# second_model.net
KiCad netlist of a schematic drawn in EAGLE
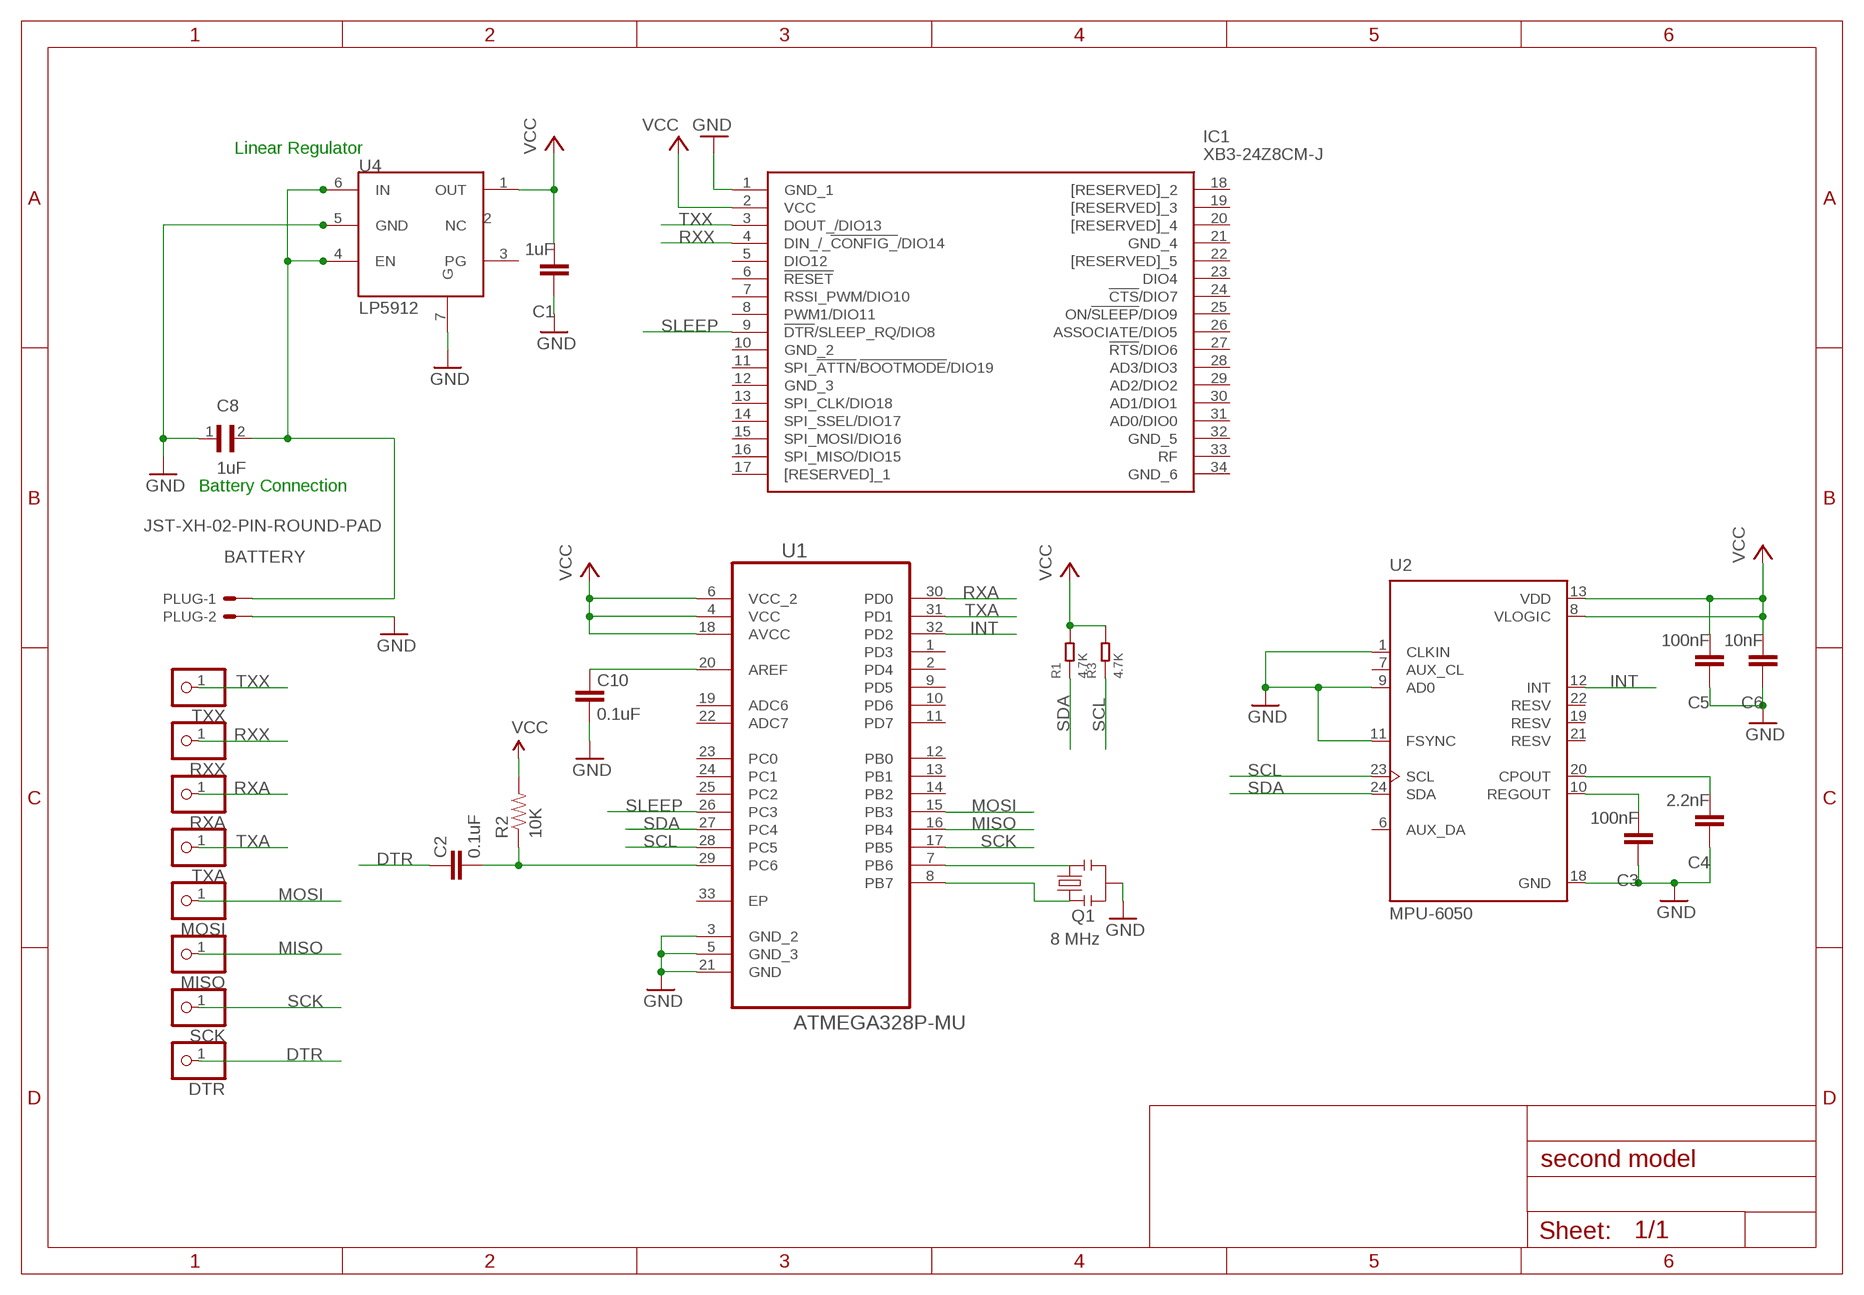
[diagram p0: schematic, sheet 1]

(export (version "E")
  (design (tool "Eeschema 10.0.6"))
  (components
    (comp (ref "C1")
      (value "1uF")
      (footprint "eagle-import:C0603")
      (libsource (lib "eagle-import") (part "C-EUC0603"))
    )
    (comp (ref "C2")
      (value "0.1uF")
      (footprint "eagle-import:0603-CAP")
      (libsource (lib "eagle-import") (part "CAP0603-CAP"))
    )
    (comp (ref "C3")
      (value "100nF")
      (footprint "eagle-import:C0603")
      (libsource (lib "eagle-import") (part "C-EUC0603"))
    )
    (comp (ref "C4")
      (value "2.2nF")
      (footprint "eagle-import:C0603")
      (libsource (lib "eagle-import") (part "C-EUC0603"))
    )
    (comp (ref "C5")
      (value "100nF")
      (footprint "eagle-import:C0603")
      (libsource (lib "eagle-import") (part "C-EUC0603"))
    )
    (comp (ref "C6")
      (value "10nF")
      (footprint "eagle-import:C0603")
      (libsource (lib "eagle-import") (part "C-EUC0603"))
    )
    (comp (ref "C8")
      (value "1uF")
      (footprint "eagle-import:CAPC1005X71N")
      (fields (field (name "MF") "AVX") (field (name "MP") "0402YD105MAT2A"))
      (libsource (lib "eagle-import") (part "0402YD105MAT2A"))
    )
    (comp (ref "C10")
      (value "0.1uF")
      (footprint "eagle-import:0603-CAP")
      (libsource (lib "eagle-import") (part "CAP0603-CAP"))
    )
    (comp (ref "DTR")
      (value "DTR")
      (footprint "eagle-import:1X01")
      (libsource (lib "eagle-import") (part "PINHD-1X1"))
    )
    (comp (ref "IC1")
      (value "XB3-24Z8CM-J")
      (footprint "eagle-import:XB324Z8CMJ")
      (fields (field (name "MOUSER_PART_NUMBER") "888-XB3-24Z8CM-J"))
      (libsource (lib "eagle-import") (part "XB3-24Z8CM-J"))
    )
    (comp (ref "MISO")
      (value "PINHD-1X1")
      (footprint "eagle-import:1X01")
      (libsource (lib "eagle-import") (part "PINHD-1X1"))
    )
    (comp (ref "MOSI")
      (value "PINHD-1X1")
      (footprint "eagle-import:1X01")
      (libsource (lib "eagle-import") (part "PINHD-1X1"))
    )
    (comp (ref "PLUG")
      (value "JST-XH-02-PIN-ROUND-PAD")
      (footprint "eagle-import:JST-XH-02-PACKAGE-ROUND-PAD")
      (libsource (lib "eagle-import") (part "JST-XH-02-PIN-ROUND-PAD"))
    )
    (comp (ref "Q1")
      (value "8 MHz")
      (footprint "eagle-import:RESONATOR-SMD-1_1")
      (libsource (lib "eagle-import") (part "RESONATOR1{colon}1"))
    )
    (comp (ref "R1")
      (value "4.7K")
      (footprint "eagle-import:R0402")
      (fields (field (name "MF") "Yageo") (field (name "MP") "RC0402JR074K7L"))
      (libsource (lib "eagle-import") (part "SMD-RES-4.7K-5%-1/16W(0402)"))
    )
    (comp (ref "R2")
      (value "10K")
      (footprint "eagle-import:0603-RES")
      (libsource (lib "eagle-import") (part "RESISTOR0603-RES"))
    )
    (comp (ref "R3")
      (value "4.7K")
      (footprint "eagle-import:R0402")
      (fields (field (name "MF") "Yageo") (field (name "MP") "RC0402JR074K7L"))
      (libsource (lib "eagle-import") (part "SMD-RES-4.7K-5%-1/16W(0402)"))
    )
    (comp (ref "RXA")
      (value "PINHD-1X1")
      (footprint "eagle-import:1X01")
      (libsource (lib "eagle-import") (part "PINHD-1X1"))
    )
    (comp (ref "RXX")
      (value "PINHD-1X1")
      (footprint "eagle-import:1X01")
      (libsource (lib "eagle-import") (part "PINHD-1X1"))
    )
    (comp (ref "SCK")
      (value "PINHD-1X1")
      (footprint "eagle-import:1X01")
      (fields (field (name "SPICEPREFIX") "X"))
      (libsource (lib "eagle-import") (part "PINHD-1X1"))
    )
    (comp (ref "TXA")
      (value "PINHD-1X1")
      (footprint "eagle-import:1X01")
      (libsource (lib "eagle-import") (part "PINHD-1X1"))
    )
    (comp (ref "TXX")
      (value "PINHD-1X1")
      (footprint "eagle-import:1X01")
      (libsource (lib "eagle-import") (part "PINHD-1X1"))
    )
    (comp (ref "U1")
      (value "ATMEGA328P-MU")
      (footprint "eagle-import:QFN50P500X500X100-33N")
      (fields (field (name "MF") "Microchip"))
      (libsource (lib "eagle-import") (part "ATMEGA328P-MU"))
    )
    (comp (ref "U2")
      (value "MPU-6050")
      (footprint "eagle-import:QFN50P400X400X95-24N")
      (fields (field (name "MF") "TDK InvenSense"))
      (libsource (lib "eagle-import") (part "MPU-6050"))
    )
    (comp (ref "U4")
      (value "LP5912")
      (footprint "eagle-import:LP5912")
      (libsource (lib "eagle-import") (part "LP5912"))
    )
  )
  (nets
    (net (code "1") (name "/BATTERY") (class "Default")
      (node (ref "C8") (pin "2") (pinfunction "2_2") (pintype "passive"))
      (node (ref "PLUG") (pin "1") (pinfunction "S_1") (pintype "passive"))
      (node (ref "U4") (pin "4") (pinfunction "EN_4") (pintype "bidirectional"))
      (node (ref "U4") (pin "6") (pinfunction "IN_6") (pintype "power_in"))
    )
    (net (code "2") (name "/DTR") (class "Default")
      (node (ref "C2") (pin "2") (pinfunction "2_2") (pintype "passive"))
      (node (ref "DTR") (pin "1") (pinfunction "1_1") (pintype "passive"))
    )
    (net (code "3") (name "/INT") (class "Default")
      (node (ref "U1") (pin "32") (pinfunction "PD2_32") (pintype "bidirectional"))
      (node (ref "U2") (pin "12") (pinfunction "INT_12") (pintype "output"))
    )
    (net (code "4") (name "/MISO") (class "Default")
      (node (ref "MISO") (pin "1") (pinfunction "1_1") (pintype "passive"))
      (node (ref "U1") (pin "16") (pinfunction "PB4_16") (pintype "bidirectional"))
    )
    (net (code "5") (name "/MOSI") (class "Default")
      (node (ref "MOSI") (pin "1") (pinfunction "1_1") (pintype "passive"))
      (node (ref "U1") (pin "15") (pinfunction "PB3_15") (pintype "bidirectional"))
    )
    (net (code "6") (name "/RXA") (class "Default")
      (node (ref "RXA") (pin "1") (pinfunction "1_1") (pintype "passive"))
      (node (ref "U1") (pin "30") (pinfunction "PD0_30") (pintype "bidirectional"))
    )
    (net (code "7") (name "/RXX") (class "Default")
      (node (ref "IC1") (pin "4") (pinfunction "DIN_/_~{CONFIG_}/DIO14_4") (pintype "bidirectional"))
      (node (ref "RXX") (pin "1") (pinfunction "1_1") (pintype "passive"))
    )
    (net (code "8") (name "/SCK") (class "Default")
      (node (ref "SCK") (pin "1") (pinfunction "1_1") (pintype "passive"))
      (node (ref "U1") (pin "17") (pinfunction "PB5_17") (pintype "bidirectional"))
    )
    (net (code "9") (name "/SCL") (class "Default")
      (node (ref "R3") (pin "1") (pinfunction "1_1") (pintype "passive"))
      (node (ref "U1") (pin "28") (pinfunction "PC5_28") (pintype "bidirectional"))
      (node (ref "U2") (pin "23") (pinfunction "SCL_23") (pintype "input"))
    )
    (net (code "10") (name "/SDA") (class "Default")
      (node (ref "R1") (pin "1") (pinfunction "1_1") (pintype "passive"))
      (node (ref "U1") (pin "27") (pinfunction "PC4_27") (pintype "bidirectional"))
      (node (ref "U2") (pin "24") (pinfunction "SDA_24") (pintype "bidirectional"))
    )
    (net (code "11") (name "/SLEEP") (class "Default")
      (node (ref "IC1") (pin "9") (pinfunction "~{DTR}/SLEEP_RQ/DIO8_9") (pintype "bidirectional"))
      (node (ref "U1") (pin "26") (pinfunction "PC3_26") (pintype "bidirectional"))
    )
    (net (code "12") (name "/TXA") (class "Default")
      (node (ref "TXA") (pin "1") (pinfunction "1_1") (pintype "passive"))
      (node (ref "U1") (pin "31") (pinfunction "PD1_31") (pintype "bidirectional"))
    )
    (net (code "13") (name "/TXX") (class "Default")
      (node (ref "IC1") (pin "3") (pinfunction "DOUT_/DIO13_3") (pintype "bidirectional"))
      (node (ref "TXX") (pin "1") (pinfunction "1_1") (pintype "passive"))
    )
    (net (code "14") (name "GND") (class "Default")
      (node (ref "C1") (pin "1") (pinfunction "1_1") (pintype "passive"))
      (node (ref "C10") (pin "1") (pinfunction "1_1") (pintype "passive"))
      (node (ref "C3") (pin "1") (pinfunction "1_1") (pintype "passive"))
      (node (ref "C4") (pin "1") (pinfunction "1_1") (pintype "passive"))
      (node (ref "C5") (pin "1") (pinfunction "1_1") (pintype "passive"))
      (node (ref "C6") (pin "1") (pinfunction "1_1") (pintype "passive"))
      (node (ref "C8") (pin "1") (pinfunction "1_1") (pintype "passive"))
      (node (ref "IC1") (pin "1") (pinfunction "GND_1_1") (pintype "bidirectional"))
      (node (ref "PLUG") (pin "2") (pinfunction "S_2") (pintype "passive"))
      (node (ref "Q1") (pin "2") (pinfunction "2_2") (pintype "passive"))
      (node (ref "U1") (pin "21") (pinfunction "GND_21") (pintype "passive"))
      (node (ref "U1") (pin "3") (pinfunction "GND_2_3") (pintype "passive"))
      (node (ref "U1") (pin "5") (pinfunction "GND_3_5") (pintype "passive"))
      (node (ref "U2") (pin "1") (pinfunction "CLKIN_1") (pintype "input"))
      (node (ref "U2") (pin "11") (pinfunction "FSYNC_11") (pintype "input"))
      (node (ref "U2") (pin "18") (pinfunction "GND_18") (pintype "power_in"))
      (node (ref "U2") (pin "9") (pinfunction "AD0_9") (pintype "input"))
      (node (ref "U4") (pin "5") (pinfunction "GND_5") (pintype "power_in"))
      (node (ref "U4") (pin "7") (pinfunction "G_7") (pintype "bidirectional"))
    )
    (net (code "15") (name "Net-(U1-AREF)") (class "Default")
      (node (ref "C10") (pin "2") (pinfunction "2_2") (pintype "passive"))
      (node (ref "U1") (pin "20") (pinfunction "AREF_20") (pintype "input"))
    )
    (net (code "16") (name "Net-(U1-PB6)") (class "Default")
      (node (ref "Q1") (pin "3") (pinfunction "3_3") (pintype "passive"))
      (node (ref "U1") (pin "7") (pinfunction "PB6_7") (pintype "bidirectional"))
    )
    (net (code "17") (name "Net-(U1-PB7)") (class "Default")
      (node (ref "Q1") (pin "1") (pinfunction "1_1") (pintype "passive"))
      (node (ref "U1") (pin "8") (pinfunction "PB7_8") (pintype "bidirectional"))
    )
    (net (code "18") (name "Net-(U1-PC6)") (class "Default")
      (node (ref "C2") (pin "1") (pinfunction "1_1") (pintype "passive"))
      (node (ref "R2") (pin "1") (pinfunction "1_1") (pintype "passive"))
      (node (ref "U1") (pin "29") (pinfunction "PC6_29") (pintype "bidirectional"))
    )
    (net (code "19") (name "Net-(U2-CPOUT)") (class "Default")
      (node (ref "C4") (pin "2") (pinfunction "2_2") (pintype "passive"))
      (node (ref "U2") (pin "20") (pinfunction "CPOUT_20") (pintype "passive"))
    )
    (net (code "20") (name "Net-(U2-REGOUT)") (class "Default")
      (node (ref "C3") (pin "2") (pinfunction "2_2") (pintype "passive"))
      (node (ref "U2") (pin "10") (pinfunction "REGOUT_10") (pintype "passive"))
    )
    (net (code "21") (name "VCC") (class "Default")
      (node (ref "C1") (pin "2") (pinfunction "2_2") (pintype "passive"))
      (node (ref "C5") (pin "2") (pinfunction "2_2") (pintype "passive"))
      (node (ref "C6") (pin "2") (pinfunction "2_2") (pintype "passive"))
      (node (ref "IC1") (pin "2") (pinfunction "VCC_2") (pintype "bidirectional"))
      (node (ref "R1") (pin "2") (pinfunction "2_2") (pintype "passive"))
      (node (ref "R2") (pin "2") (pinfunction "2_2") (pintype "passive"))
      (node (ref "R3") (pin "2") (pinfunction "2_2") (pintype "passive"))
      (node (ref "U1") (pin "18") (pinfunction "AVCC_18") (pintype "power_in"))
      (node (ref "U1") (pin "4") (pinfunction "VCC_4") (pintype "power_in"))
      (node (ref "U1") (pin "6") (pinfunction "VCC_2_6") (pintype "power_in"))
      (node (ref "U2") (pin "13") (pinfunction "VDD_13") (pintype "power_in"))
      (node (ref "U2") (pin "8") (pinfunction "VLOGIC_8") (pintype "power_in"))
      (node (ref "U4") (pin "1") (pinfunction "OUT_1") (pintype "power_in"))
    )
    (net (code "22") (name "unconnected-(IC1-AD0{slash}DIO0-Pad31)") (class "Default")
      (node (ref "IC1") (pin "31") (pinfunction "AD0/DIO0_31") (pintype "bidirectional"))
    )
    (net (code "23") (name "unconnected-(IC1-AD1{slash}DIO1-Pad30)") (class "Default")
      (node (ref "IC1") (pin "30") (pinfunction "AD1/DIO1_30") (pintype "bidirectional"))
    )
    (net (code "24") (name "unconnected-(IC1-AD2{slash}DIO2-Pad29)") (class "Default")
      (node (ref "IC1") (pin "29") (pinfunction "AD2/DIO2_29") (pintype "bidirectional"))
    )
    (net (code "25") (name "unconnected-(IC1-AD3{slash}DIO3-Pad28)") (class "Default")
      (node (ref "IC1") (pin "28") (pinfunction "AD3/DIO3_28") (pintype "bidirectional"))
    )
    (net (code "26") (name "unconnected-(IC1-ASSOCIATE{slash}DIO5-Pad26)") (class "Default")
      (node (ref "IC1") (pin "26") (pinfunction "ASSOCIATE/DIO5_26") (pintype "bidirectional"))
    )
    (net (code "27") (name "unconnected-(IC1-DIO4-Pad23)") (class "Default")
      (node (ref "IC1") (pin "23") (pinfunction "DIO4_23") (pintype "bidirectional"))
    )
    (net (code "28") (name "unconnected-(IC1-DIO12-Pad5)") (class "Default")
      (node (ref "IC1") (pin "5") (pinfunction "DIO12_5") (pintype "bidirectional"))
    )
    (net (code "29") (name "unconnected-(IC1-GND_2-Pad10)") (class "Default")
      (node (ref "IC1") (pin "10") (pinfunction "GND_2_10") (pintype "bidirectional"))
    )
    (net (code "30") (name "unconnected-(IC1-GND_3-Pad12)") (class "Default")
      (node (ref "IC1") (pin "12") (pinfunction "GND_3_12") (pintype "bidirectional"))
    )
    (net (code "31") (name "unconnected-(IC1-GND_4-Pad21)") (class "Default")
      (node (ref "IC1") (pin "21") (pinfunction "GND_4_21") (pintype "bidirectional"))
    )
    (net (code "32") (name "unconnected-(IC1-GND_5-Pad32)") (class "Default")
      (node (ref "IC1") (pin "32") (pinfunction "GND_5_32") (pintype "bidirectional"))
    )
    (net (code "33") (name "unconnected-(IC1-GND_6-Pad34)") (class "Default")
      (node (ref "IC1") (pin "34") (pinfunction "GND_6_34") (pintype "bidirectional"))
    )
    (net (code "34") (name "unconnected-(IC1-ON{slash}~{SLEEP}{slash}DIO9-Pad25)") (class "Default")
      (node (ref "IC1") (pin "25") (pinfunction "ON/~{SLEEP}/DIO9_25") (pintype "bidirectional"))
    )
    (net (code "35") (name "unconnected-(IC1-PWM1{slash}DIO11-Pad8)") (class "Default")
      (node (ref "IC1") (pin "8") (pinfunction "PWM1/DIO11_8") (pintype "bidirectional"))
    )
    (net (code "36") (name "unconnected-(IC1-RF-Pad33)") (class "Default")
      (node (ref "IC1") (pin "33") (pinfunction "RF_33") (pintype "bidirectional"))
    )
    (net (code "37") (name "unconnected-(IC1-RSSI_PWM{slash}DIO10-Pad7)") (class "Default")
      (node (ref "IC1") (pin "7") (pinfunction "RSSI_PWM/DIO10_7") (pintype "bidirectional"))
    )
    (net (code "38") (name "unconnected-(IC1-SPI_CLK{slash}DIO18-Pad13)") (class "Default")
      (node (ref "IC1") (pin "13") (pinfunction "SPI_CLK/DIO18_13") (pintype "bidirectional"))
    )
    (net (code "39") (name "unconnected-(IC1-SPI_MISO{slash}DIO15-Pad16)") (class "Default")
      (node (ref "IC1") (pin "16") (pinfunction "SPI_MISO/DIO15_16") (pintype "bidirectional"))
    )
    (net (code "40") (name "unconnected-(IC1-SPI_MOSI{slash}DIO16-Pad15)") (class "Default")
      (node (ref "IC1") (pin "15") (pinfunction "SPI_MOSI/DIO16_15") (pintype "bidirectional"))
    )
    (net (code "41") (name "unconnected-(IC1-SPI_SSEL{slash}DIO17-Pad14)") (class "Default")
      (node (ref "IC1") (pin "14") (pinfunction "SPI_SSEL/DIO17_14") (pintype "bidirectional"))
    )
    (net (code "42") (name "unconnected-(IC1-SPI_~{ATTN}{slash}~{BOOTMODE}{slash}DIO19-Pad11)") (class "Default")
      (node (ref "IC1") (pin "11") (pinfunction "SPI_~{ATTN}/~{BOOTMODE}/DIO19_11") (pintype "bidirectional"))
    )
    (net (code "43") (name "unconnected-(IC1-[RESERVED]_1-Pad17)") (class "Default")
      (node (ref "IC1") (pin "17") (pinfunction "[RESERVED]_1_17") (pintype "bidirectional"))
    )
    (net (code "44") (name "unconnected-(IC1-[RESERVED]_2-Pad18)") (class "Default")
      (node (ref "IC1") (pin "18") (pinfunction "[RESERVED]_2_18") (pintype "bidirectional"))
    )
    (net (code "45") (name "unconnected-(IC1-[RESERVED]_3-Pad19)") (class "Default")
      (node (ref "IC1") (pin "19") (pinfunction "[RESERVED]_3_19") (pintype "bidirectional"))
    )
    (net (code "46") (name "unconnected-(IC1-[RESERVED]_4-Pad20)") (class "Default")
      (node (ref "IC1") (pin "20") (pinfunction "[RESERVED]_4_20") (pintype "bidirectional"))
    )
    (net (code "47") (name "unconnected-(IC1-[RESERVED]_5-Pad22)") (class "Default")
      (node (ref "IC1") (pin "22") (pinfunction "[RESERVED]_5_22") (pintype "bidirectional"))
    )
    (net (code "48") (name "unconnected-(IC1-~{CTS}{slash}DIO7-Pad24)") (class "Default")
      (node (ref "IC1") (pin "24") (pinfunction "~{CTS}/DIO7_24") (pintype "bidirectional"))
    )
    (net (code "49") (name "unconnected-(IC1-~{RESET}-Pad6)") (class "Default")
      (node (ref "IC1") (pin "6") (pinfunction "~{RESET}_6") (pintype "bidirectional"))
    )
    (net (code "50") (name "unconnected-(IC1-~{RTS}{slash}DIO6-Pad27)") (class "Default")
      (node (ref "IC1") (pin "27") (pinfunction "~{RTS}/DIO6_27") (pintype "bidirectional"))
    )
    (net (code "51") (name "unconnected-(U1-ADC6-Pad19)") (class "Default")
      (node (ref "U1") (pin "19") (pinfunction "ADC6_19") (pintype "input"))
    )
    (net (code "52") (name "unconnected-(U1-ADC7-Pad22)") (class "Default")
      (node (ref "U1") (pin "22") (pinfunction "ADC7_22") (pintype "input"))
    )
    (net (code "53") (name "unconnected-(U1-EP-Pad33)") (class "Default")
      (node (ref "U1") (pin "33") (pinfunction "EP_33") (pintype "passive"))
    )
    (net (code "54") (name "unconnected-(U1-PB0-Pad12)") (class "Default")
      (node (ref "U1") (pin "12") (pinfunction "PB0_12") (pintype "bidirectional"))
    )
    (net (code "55") (name "unconnected-(U1-PB1-Pad13)") (class "Default")
      (node (ref "U1") (pin "13") (pinfunction "PB1_13") (pintype "bidirectional"))
    )
    (net (code "56") (name "unconnected-(U1-PB2-Pad14)") (class "Default")
      (node (ref "U1") (pin "14") (pinfunction "PB2_14") (pintype "bidirectional"))
    )
    (net (code "57") (name "unconnected-(U1-PC0-Pad23)") (class "Default")
      (node (ref "U1") (pin "23") (pinfunction "PC0_23") (pintype "bidirectional"))
    )
    (net (code "58") (name "unconnected-(U1-PC1-Pad24)") (class "Default")
      (node (ref "U1") (pin "24") (pinfunction "PC1_24") (pintype "bidirectional"))
    )
    (net (code "59") (name "unconnected-(U1-PC2-Pad25)") (class "Default")
      (node (ref "U1") (pin "25") (pinfunction "PC2_25") (pintype "bidirectional"))
    )
    (net (code "60") (name "unconnected-(U1-PD3-Pad1)") (class "Default")
      (node (ref "U1") (pin "1") (pinfunction "PD3_1") (pintype "bidirectional"))
    )
    (net (code "61") (name "unconnected-(U1-PD4-Pad2)") (class "Default")
      (node (ref "U1") (pin "2") (pinfunction "PD4_2") (pintype "bidirectional"))
    )
    (net (code "62") (name "unconnected-(U1-PD5-Pad9)") (class "Default")
      (node (ref "U1") (pin "9") (pinfunction "PD5_9") (pintype "bidirectional"))
    )
    (net (code "63") (name "unconnected-(U1-PD6-Pad10)") (class "Default")
      (node (ref "U1") (pin "10") (pinfunction "PD6_10") (pintype "bidirectional"))
    )
    (net (code "64") (name "unconnected-(U1-PD7-Pad11)") (class "Default")
      (node (ref "U1") (pin "11") (pinfunction "PD7_11") (pintype "bidirectional"))
    )
    (net (code "65") (name "unconnected-(U2-AUX_CL-Pad7)") (class "Default")
      (node (ref "U2") (pin "7") (pinfunction "AUX_CL_7") (pintype "input"))
    )
    (net (code "66") (name "unconnected-(U2-AUX_DA-Pad6)") (class "Default")
      (node (ref "U2") (pin "6") (pinfunction "AUX_DA_6") (pintype "bidirectional"))
    )
    (net (code "67") (name "unconnected-(U2-RESV-Pad19)") (class "Default")
      (node (ref "U2") (pin "19") (pinfunction "RESV_19") (pintype "passive"))
    )
    (net (code "68") (name "unconnected-(U2-RESV-Pad21)") (class "Default")
      (node (ref "U2") (pin "21") (pinfunction "RESV_21") (pintype "passive"))
    )
    (net (code "69") (name "unconnected-(U2-RESV-Pad22)") (class "Default")
      (node (ref "U2") (pin "22") (pinfunction "RESV_22") (pintype "passive"))
    )
    (net (code "70") (name "unconnected-(U4-NC-Pad2)") (class "Default")
      (node (ref "U4") (pin "2") (pinfunction "NC_2") (pintype "bidirectional"))
    )
    (net (code "71") (name "unconnected-(U4-PG-Pad3)") (class "Default")
      (node (ref "U4") (pin "3") (pinfunction "PG_3") (pintype "bidirectional"))
    )
  )
)
